# waterLevelController.net
KiCad netlist of a schematic drawn in EAGLE
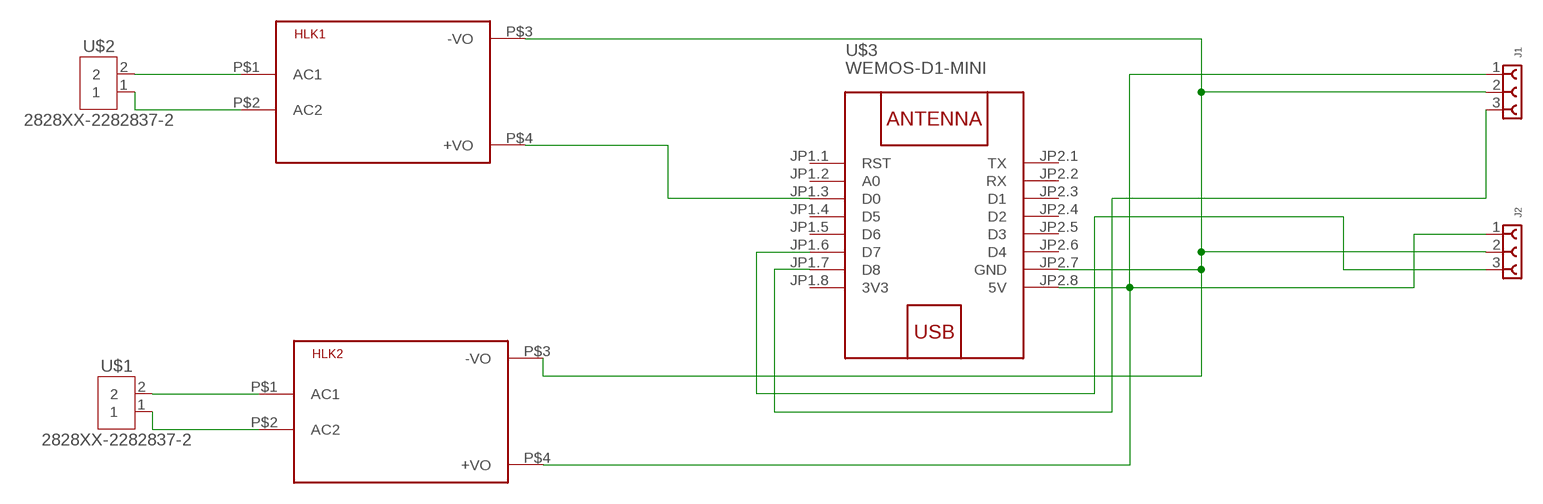
[diagram p0: schematic, sheet 1]

(export (version "E")
  (design (tool "Eeschema 10.0.6"))
  (components
    (comp (ref "HLK1")
      (value "HLK-PM013W")
      (footprint "eagle-import:HLK-PM01")
      (libsource (lib "eagle-import") (part "HLK-PM013W"))
    )
    (comp (ref "HLK2")
      (value "HLK-PM013W")
      (footprint "eagle-import:HLK-PM01")
      (libsource (lib "eagle-import") (part "HLK-PM013W"))
    )
    (comp (ref "J1")
      (value "6130XX11821_61300311821")
      (footprint "eagle-import:61300311821")
      (libsource (lib "eagle-import") (part "6130XX11821_61300311821"))
    )
    (comp (ref "J2")
      (value "6130XX11821_61300311821")
      (footprint "eagle-import:61300311821")
      (libsource (lib "eagle-import") (part "6130XX11821_61300311821"))
    )
    (comp (ref "U$1")
      (value "2828XX-2282837-2")
      (footprint "eagle-import:TERMBLK_508-2N")
      (fields (field (name "MANUFACTURER") "TE Connectivity") (field (name "MPN") "282837-2"))
      (libsource (lib "eagle-import") (part "2828XX-2282837-2"))
    )
    (comp (ref "U$2")
      (value "2828XX-2282837-2")
      (footprint "eagle-import:TERMBLK_508-2N")
      (fields (field (name "MANUFACTURER") "TE Connectivity") (field (name "MPN") "282837-2"))
      (libsource (lib "eagle-import") (part "2828XX-2282837-2"))
    )
    (comp (ref "U$3")
      (value "WEMOS-D1-MINI")
      (footprint "eagle-import:WEMOS-D1-MINI")
      (libsource (lib "eagle-import") (part "WEMOS-D1-MINI"))
    )
  )
  (nets
    (net (code "1") (name "/3V3") (class "Default")
      (node (ref "U$3") (pin "JP1.8") (pinfunction "3V3_JP1.8") (pintype "power_in"))
    )
    (net (code "2") (name "Net-(HLK1-+VO)") (class "Default")
      (node (ref "HLK1") (pin "P$4") (pinfunction "+VO_P$4") (pintype "bidirectional"))
      (node (ref "U$3") (pin "JP1.3") (pinfunction "D0_JP1.3") (pintype "bidirectional"))
    )
    (net (code "3") (name "Net-(HLK1--VO)") (class "Default")
      (node (ref "HLK1") (pin "P$3") (pinfunction "-VO_P$3") (pintype "bidirectional"))
      (node (ref "HLK2") (pin "P$3") (pinfunction "-VO_P$3") (pintype "bidirectional"))
      (node (ref "J1") (pin "2") (pinfunction "2_2") (pintype "passive"))
      (node (ref "J2") (pin "2") (pinfunction "2_2") (pintype "passive"))
      (node (ref "U$3") (pin "JP2.7") (pinfunction "GND_JP2.7") (pintype "power_in"))
    )
    (net (code "4") (name "Net-(HLK1-AC1)") (class "Default")
      (node (ref "HLK1") (pin "P$1") (pinfunction "AC1_P$1") (pintype "bidirectional"))
      (node (ref "U$2") (pin "2") (pinfunction "2_2") (pintype "bidirectional"))
    )
    (net (code "5") (name "Net-(HLK1-AC2)") (class "Default")
      (node (ref "HLK1") (pin "P$2") (pinfunction "AC2_P$2") (pintype "bidirectional"))
      (node (ref "U$2") (pin "1") (pinfunction "1_1") (pintype "bidirectional"))
    )
    (net (code "6") (name "Net-(HLK2-+VO)") (class "Default")
      (node (ref "HLK2") (pin "P$4") (pinfunction "+VO_P$4") (pintype "bidirectional"))
      (node (ref "J1") (pin "1") (pinfunction "1_1") (pintype "passive"))
      (node (ref "J2") (pin "1") (pinfunction "1_1") (pintype "passive"))
      (node (ref "U$3") (pin "JP2.8") (pinfunction "5V_JP2.8") (pintype "power_in"))
    )
    (net (code "7") (name "Net-(HLK2-AC1)") (class "Default")
      (node (ref "HLK2") (pin "P$1") (pinfunction "AC1_P$1") (pintype "bidirectional"))
      (node (ref "U$1") (pin "2") (pinfunction "2_2") (pintype "bidirectional"))
    )
    (net (code "8") (name "Net-(HLK2-AC2)") (class "Default")
      (node (ref "HLK2") (pin "P$2") (pinfunction "AC2_P$2") (pintype "bidirectional"))
      (node (ref "U$1") (pin "1") (pinfunction "1_1") (pintype "bidirectional"))
    )
    (net (code "9") (name "Net-(U$3-D7)") (class "Default")
      (node (ref "J2") (pin "3") (pinfunction "3_3") (pintype "passive"))
      (node (ref "U$3") (pin "JP1.6") (pinfunction "D7_JP1.6") (pintype "bidirectional"))
    )
    (net (code "10") (name "Net-(U$3-D8)") (class "Default")
      (node (ref "J1") (pin "3") (pinfunction "3_3") (pintype "passive"))
      (node (ref "U$3") (pin "JP1.7") (pinfunction "D8_JP1.7") (pintype "bidirectional"))
    )
    (net (code "11") (name "unconnected-(U$3-A0-PadJP1.2)") (class "Default")
      (node (ref "U$3") (pin "JP1.2") (pinfunction "A0_JP1.2") (pintype "bidirectional"))
    )
    (net (code "12") (name "unconnected-(U$3-D1-PadJP2.3)") (class "Default")
      (node (ref "U$3") (pin "JP2.3") (pinfunction "D1_JP2.3") (pintype "bidirectional"))
    )
    (net (code "13") (name "unconnected-(U$3-D2-PadJP2.4)") (class "Default")
      (node (ref "U$3") (pin "JP2.4") (pinfunction "D2_JP2.4") (pintype "bidirectional"))
    )
    (net (code "14") (name "unconnected-(U$3-D3-PadJP2.5)") (class "Default")
      (node (ref "U$3") (pin "JP2.5") (pinfunction "D3_JP2.5") (pintype "bidirectional"))
    )
    (net (code "15") (name "unconnected-(U$3-D4-PadJP2.6)") (class "Default")
      (node (ref "U$3") (pin "JP2.6") (pinfunction "D4_JP2.6") (pintype "bidirectional"))
    )
    (net (code "16") (name "unconnected-(U$3-D5-PadJP1.4)") (class "Default")
      (node (ref "U$3") (pin "JP1.4") (pinfunction "D5_JP1.4") (pintype "bidirectional"))
    )
    (net (code "17") (name "unconnected-(U$3-D6-PadJP1.5)") (class "Default")
      (node (ref "U$3") (pin "JP1.5") (pinfunction "D6_JP1.5") (pintype "bidirectional"))
    )
    (net (code "18") (name "unconnected-(U$3-RST-PadJP1.1)") (class "Default")
      (node (ref "U$3") (pin "JP1.1") (pinfunction "RST_JP1.1") (pintype "bidirectional"))
    )
    (net (code "19") (name "unconnected-(U$3-RX-PadJP2.2)") (class "Default")
      (node (ref "U$3") (pin "JP2.2") (pinfunction "RX_JP2.2") (pintype "bidirectional"))
    )
    (net (code "20") (name "unconnected-(U$3-TX-PadJP2.1)") (class "Default")
      (node (ref "U$3") (pin "JP2.1") (pinfunction "TX_JP2.1") (pintype "bidirectional"))
    )
  )
)
